# Connector.net
KiCad netlist of a schematic drawn in Altium Designer
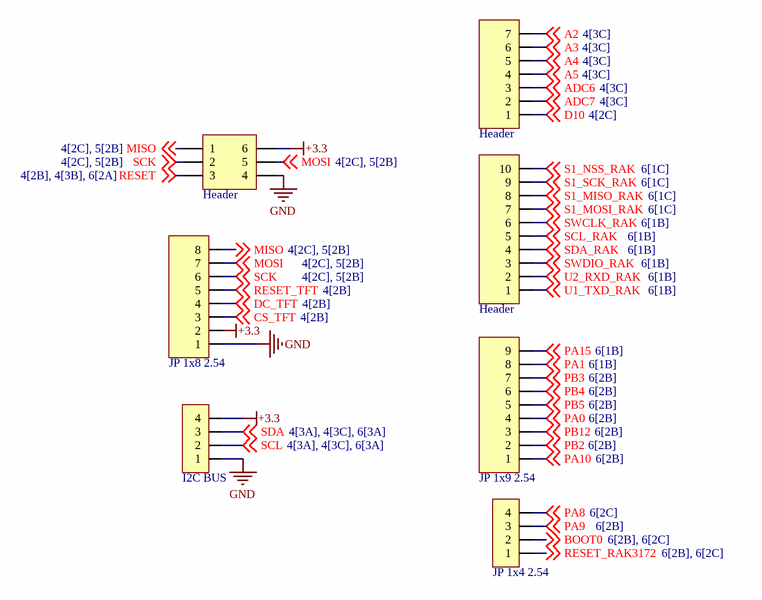
[diagram p0: Connector.SchDoc]

(export (version "E")
  (design (tool "Eeschema 10.0.6"))
  (components
    (comp (ref "JP1")
      (value "Header")
      (footprint "JP 1x7 CT")
      (description "Cắm")
      (libsource (lib "Jump") (part "JP 1x7 2.54 Cai Thang"))
    )
    (comp (ref "JP2")
      (value "Header")
      (footprint "JP 2x3 DT")
      (description "Cắm")
      (libsource (lib "Jump") (part "JP 2x3 2.54 Duc Thang"))
    )
    (comp (ref "JP3")
      (value "Header")
      (footprint "JP 1x10 CT")
      (description "Cắm")
      (libsource (lib "Jump") (part "JP 1x10 2.54 Cai Thang"))
    )
    (comp (ref "JP4")
      (value "JP 1x8 2.54")
      (footprint "JP 1x8 CT")
      (description "Cắm")
      (libsource (lib "Jump") (part "JP 1x8 2.54 Cai Thang"))
    )
    (comp (ref "JP5")
      (value "JP 1x9 2.54")
      (footprint "JP 1x9 CT")
      (description "Cắm")
      (libsource (lib "Jump") (part "JP 1x9 2.54 Cai Thang"))
    )
    (comp (ref "JP6")
      (value "I2C BUS")
      (footprint "JP 1x4 CT")
      (description "Cắm")
      (libsource (lib "Jump") (part "JP 1x4 2.54 Cai Thang"))
    )
    (comp (ref "JP7")
      (value "JP 1x4 2.54")
      (footprint "JP 1x4 CT")
      (description "Cắm")
      (libsource (lib "Jump") (part "JP 1x4 2.54 Cai Thang"))
    )
  )
  (nets
    (net (code "1") (name "+3.3") (class "Default")
      (node (ref "JP2") (pin "6") (pinfunction "6_6") (pintype "passive"))
      (node (ref "JP4") (pin "2") (pinfunction "2_2") (pintype "passive"))
      (node (ref "JP6") (pin "4") (pinfunction "4_4") (pintype "passive"))
    )
    (net (code "2") (name "A2") (class "Default")
      (node (ref "JP1") (pin "7") (pinfunction "7_7") (pintype "passive"))
    )
    (net (code "3") (name "A3") (class "Default")
      (node (ref "JP1") (pin "6") (pinfunction "6_6") (pintype "passive"))
    )
    (net (code "4") (name "A4") (class "Default")
      (node (ref "JP1") (pin "5") (pinfunction "5_5") (pintype "passive"))
    )
    (net (code "5") (name "A5") (class "Default")
      (node (ref "JP1") (pin "4") (pinfunction "4_4") (pintype "passive"))
    )
    (net (code "6") (name "ADC6") (class "Default")
      (node (ref "JP1") (pin "3") (pinfunction "3_3") (pintype "passive"))
    )
    (net (code "7") (name "ADC7") (class "Default")
      (node (ref "JP1") (pin "2") (pinfunction "2_2") (pintype "passive"))
    )
    (net (code "8") (name "BOOT0") (class "Default")
      (node (ref "JP7") (pin "2") (pinfunction "2_2") (pintype "passive"))
    )
    (net (code "9") (name "CS_TFT") (class "Default")
      (node (ref "JP4") (pin "3") (pinfunction "3_3") (pintype "passive"))
    )
    (net (code "10") (name "D10") (class "Default")
      (node (ref "JP1") (pin "1") (pinfunction "1_1") (pintype "passive"))
    )
    (net (code "11") (name "DC_TFT") (class "Default")
      (node (ref "JP4") (pin "4") (pinfunction "4_4") (pintype "passive"))
    )
    (net (code "12") (name "GND") (class "Default")
      (node (ref "JP2") (pin "4") (pinfunction "4_4") (pintype "passive"))
      (node (ref "JP4") (pin "1") (pinfunction "1_1") (pintype "passive"))
      (node (ref "JP6") (pin "1") (pinfunction "1_1") (pintype "passive"))
    )
    (net (code "13") (name "MISO") (class "Default")
      (node (ref "JP2") (pin "1") (pinfunction "1_1") (pintype "passive"))
      (node (ref "JP4") (pin "8") (pinfunction "8_8") (pintype "passive"))
    )
    (net (code "14") (name "MOSI") (class "Default")
      (node (ref "JP2") (pin "5") (pinfunction "5_5") (pintype "passive"))
      (node (ref "JP4") (pin "7") (pinfunction "7_7") (pintype "passive"))
    )
    (net (code "15") (name "PA0") (class "Default")
      (node (ref "JP5") (pin "4") (pinfunction "4_4") (pintype "passive"))
    )
    (net (code "16") (name "PA1") (class "Default")
      (node (ref "JP5") (pin "8") (pinfunction "8_8") (pintype "passive"))
    )
    (net (code "17") (name "PA8") (class "Default")
      (node (ref "JP7") (pin "4") (pinfunction "4_4") (pintype "passive"))
    )
    (net (code "18") (name "PA9") (class "Default")
      (node (ref "JP7") (pin "3") (pinfunction "3_3") (pintype "passive"))
    )
    (net (code "19") (name "PA10") (class "Default")
      (node (ref "JP5") (pin "1") (pinfunction "1_1") (pintype "passive"))
    )
    (net (code "20") (name "PA15") (class "Default")
      (node (ref "JP5") (pin "9") (pinfunction "9_9") (pintype "passive"))
    )
    (net (code "21") (name "PB2") (class "Default")
      (node (ref "JP5") (pin "2") (pinfunction "2_2") (pintype "passive"))
    )
    (net (code "22") (name "PB3") (class "Default")
      (node (ref "JP5") (pin "7") (pinfunction "7_7") (pintype "passive"))
    )
    (net (code "23") (name "PB4") (class "Default")
      (node (ref "JP5") (pin "6") (pinfunction "6_6") (pintype "passive"))
    )
    (net (code "24") (name "PB5") (class "Default")
      (node (ref "JP5") (pin "5") (pinfunction "5_5") (pintype "passive"))
    )
    (net (code "25") (name "PB12") (class "Default")
      (node (ref "JP5") (pin "3") (pinfunction "3_3") (pintype "passive"))
    )
    (net (code "26") (name "RESET") (class "Default")
      (node (ref "JP2") (pin "3") (pinfunction "3_3") (pintype "passive"))
    )
    (net (code "27") (name "RESET_RAK3172") (class "Default")
      (node (ref "JP7") (pin "1") (pinfunction "1_1") (pintype "passive"))
    )
    (net (code "28") (name "RESET_TFT") (class "Default")
      (node (ref "JP4") (pin "5") (pinfunction "5_5") (pintype "passive"))
    )
    (net (code "29") (name "S1_MISO_RAK") (class "Default")
      (node (ref "JP3") (pin "8") (pinfunction "8_8") (pintype "passive"))
    )
    (net (code "30") (name "S1_MOSI_RAK") (class "Default")
      (node (ref "JP3") (pin "7") (pinfunction "7_7") (pintype "passive"))
    )
    (net (code "31") (name "S1_NSS_RAK") (class "Default")
      (node (ref "JP3") (pin "10") (pinfunction "10_10") (pintype "passive"))
    )
    (net (code "32") (name "S1_SCK_RAK") (class "Default")
      (node (ref "JP3") (pin "9") (pinfunction "9_9") (pintype "passive"))
    )
    (net (code "33") (name "SCK") (class "Default")
      (node (ref "JP2") (pin "2") (pinfunction "2_2") (pintype "passive"))
      (node (ref "JP4") (pin "6") (pinfunction "6_6") (pintype "passive"))
    )
    (net (code "34") (name "SCL") (class "Default")
      (node (ref "JP6") (pin "2") (pinfunction "2_2") (pintype "passive"))
    )
    (net (code "35") (name "SCL_RAK") (class "Default")
      (node (ref "JP3") (pin "5") (pinfunction "5_5") (pintype "passive"))
    )
    (net (code "36") (name "SDA") (class "Default")
      (node (ref "JP6") (pin "3") (pinfunction "3_3") (pintype "passive"))
    )
    (net (code "37") (name "SDA_RAK") (class "Default")
      (node (ref "JP3") (pin "4") (pinfunction "4_4") (pintype "passive"))
    )
    (net (code "38") (name "SWCLK_RAK") (class "Default")
      (node (ref "JP3") (pin "6") (pinfunction "6_6") (pintype "passive"))
    )
    (net (code "39") (name "SWDIO_RAK") (class "Default")
      (node (ref "JP3") (pin "3") (pinfunction "3_3") (pintype "passive"))
    )
    (net (code "40") (name "U1_TXD_RAK") (class "Default")
      (node (ref "JP3") (pin "1") (pinfunction "1_1") (pintype "passive"))
    )
    (net (code "41") (name "U2_RXD_RAK") (class "Default")
      (node (ref "JP3") (pin "2") (pinfunction "2_2") (pintype "passive"))
    )
  )
)
